# AetherMesh_Test_Fixture_LGA_V1_0.net
KiCad netlist of a schematic drawn in EAGLE
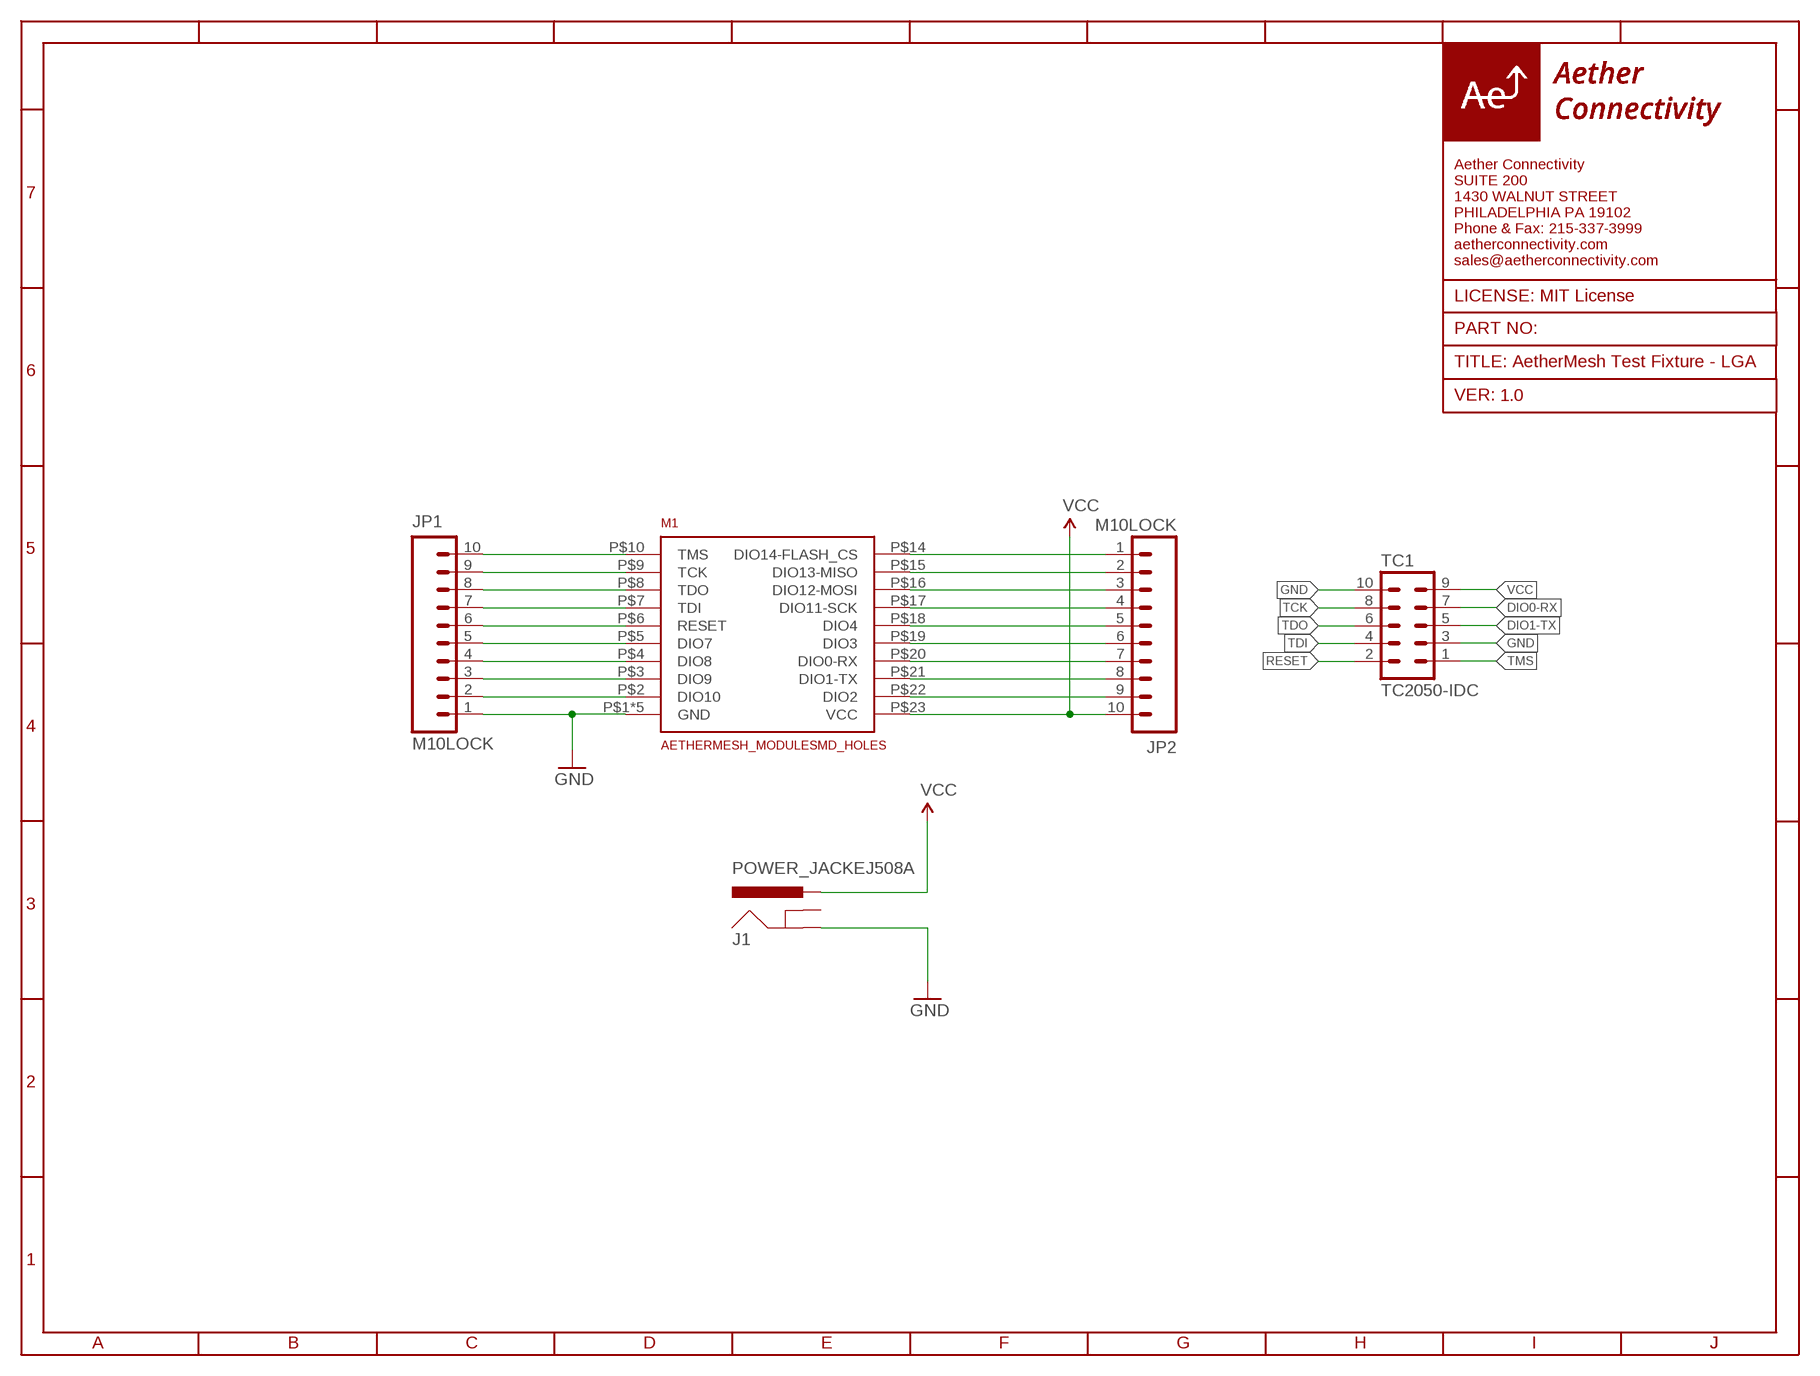
[diagram p0: schematic, sheet 1]

(export (version "E")
  (design (tool "Eeschema 10.0.6"))
  (components
    (comp (ref "J1")
      (value "POWER_JACKEJ508A")
      (footprint "eagle-import:DC_JACK_EJ508A")
      (libsource (lib "eagle-import") (part "POWER_JACKEJ508A"))
    )
    (comp (ref "JP1")
      (value "M10LOCK")
      (footprint "eagle-import:1X10_LOCK")
      (libsource (lib "eagle-import") (part "M10LOCK"))
    )
    (comp (ref "JP2")
      (value "M10LOCK")
      (footprint "eagle-import:1X10_LOCK")
      (libsource (lib "eagle-import") (part "M10LOCK"))
    )
    (comp (ref "M1")
      (value "AETHERMESH_MODULESMD_HOLES")
      (footprint "eagle-import:AETHERMESH_SMD_MOUNT_HOLES")
      (libsource (lib "eagle-import") (part "AETHERMESH_MODULESMD_HOLES"))
    )
    (comp (ref "TC1")
      (value "TC2050-IDC")
      (footprint "eagle-import:TC2050-IDC")
      (libsource (lib "eagle-import") (part "TC2050-IDC"))
    )
  )
  (nets
    (net (code "1") (name "DIO0-RX") (class "Default")
      (node (ref "JP2") (pin "7") (pinfunction "7_7") (pintype "passive"))
      (node (ref "M1") (pin "P$20") (pinfunction "DIO0-RX_P$20") (pintype "bidirectional"))
      (node (ref "TC1") (pin "7") (pinfunction "7_7") (pintype "passive"))
    )
    (net (code "2") (name "DIO1-TX") (class "Default")
      (node (ref "JP2") (pin "8") (pinfunction "8_8") (pintype "passive"))
      (node (ref "M1") (pin "P$21") (pinfunction "DIO1-TX_P$21") (pintype "bidirectional"))
      (node (ref "TC1") (pin "5") (pinfunction "5_5") (pintype "passive"))
    )
    (net (code "3") (name "GND") (class "Default")
      (node (ref "J1") (pin "1") (pinfunction "GND_1") (pintype "bidirectional"))
      (node (ref "JP1") (pin "1") (pinfunction "1_1") (pintype "passive"))
      (node (ref "M1") (pin "P$1") (pinfunction "GND_P$1") (pintype "bidirectional"))
      (node (ref "M1") (pin "P$11") (pinfunction "GND_P$11") (pintype "bidirectional"))
      (node (ref "M1") (pin "P$12") (pinfunction "GND_P$12") (pintype "bidirectional"))
      (node (ref "M1") (pin "P$13") (pinfunction "GND_P$13") (pintype "bidirectional"))
      (node (ref "M1") (pin "P$24") (pinfunction "GND_P$24") (pintype "bidirectional"))
      (node (ref "TC1") (pin "10") (pinfunction "10_10") (pintype "passive"))
      (node (ref "TC1") (pin "3") (pinfunction "3_3") (pintype "passive"))
    )
    (net (code "4") (name "Net-(M1-DIO2)") (class "Default")
      (node (ref "JP2") (pin "9") (pinfunction "9_9") (pintype "passive"))
      (node (ref "M1") (pin "P$22") (pinfunction "DIO2_P$22") (pintype "bidirectional"))
    )
    (net (code "5") (name "Net-(M1-DIO3)") (class "Default")
      (node (ref "JP2") (pin "6") (pinfunction "6_6") (pintype "passive"))
      (node (ref "M1") (pin "P$19") (pinfunction "DIO3_P$19") (pintype "bidirectional"))
    )
    (net (code "6") (name "Net-(M1-DIO4)") (class "Default")
      (node (ref "JP2") (pin "5") (pinfunction "5_5") (pintype "passive"))
      (node (ref "M1") (pin "P$18") (pinfunction "DIO4_P$18") (pintype "bidirectional"))
    )
    (net (code "7") (name "Net-(M1-DIO7)") (class "Default")
      (node (ref "JP1") (pin "5") (pinfunction "5_5") (pintype "passive"))
      (node (ref "M1") (pin "P$5") (pinfunction "DIO7_P$5") (pintype "bidirectional"))
    )
    (net (code "8") (name "Net-(M1-DIO8)") (class "Default")
      (node (ref "JP1") (pin "4") (pinfunction "4_4") (pintype "passive"))
      (node (ref "M1") (pin "P$4") (pinfunction "DIO8_P$4") (pintype "bidirectional"))
    )
    (net (code "9") (name "Net-(M1-DIO9)") (class "Default")
      (node (ref "JP1") (pin "3") (pinfunction "3_3") (pintype "passive"))
      (node (ref "M1") (pin "P$3") (pinfunction "DIO9_P$3") (pintype "bidirectional"))
    )
    (net (code "10") (name "Net-(M1-DIO10)") (class "Default")
      (node (ref "JP1") (pin "2") (pinfunction "2_2") (pintype "passive"))
      (node (ref "M1") (pin "P$2") (pinfunction "DIO10_P$2") (pintype "bidirectional"))
    )
    (net (code "11") (name "Net-(M1-DIO11-SCK)") (class "Default")
      (node (ref "JP2") (pin "4") (pinfunction "4_4") (pintype "passive"))
      (node (ref "M1") (pin "P$17") (pinfunction "DIO11-SCK_P$17") (pintype "bidirectional"))
    )
    (net (code "12") (name "Net-(M1-DIO12-MOSI)") (class "Default")
      (node (ref "JP2") (pin "3") (pinfunction "3_3") (pintype "passive"))
      (node (ref "M1") (pin "P$16") (pinfunction "DIO12-MOSI_P$16") (pintype "bidirectional"))
    )
    (net (code "13") (name "Net-(M1-DIO13-MISO)") (class "Default")
      (node (ref "JP2") (pin "2") (pinfunction "2_2") (pintype "passive"))
      (node (ref "M1") (pin "P$15") (pinfunction "DIO13-MISO_P$15") (pintype "bidirectional"))
    )
    (net (code "14") (name "Net-(M1-DIO14-FLASH_CS)") (class "Default")
      (node (ref "JP2") (pin "1") (pinfunction "1_1") (pintype "passive"))
      (node (ref "M1") (pin "P$14") (pinfunction "DIO14-FLASH_CS_P$14") (pintype "bidirectional"))
    )
    (net (code "15") (name "RESET") (class "Default")
      (node (ref "JP1") (pin "6") (pinfunction "6_6") (pintype "passive"))
      (node (ref "M1") (pin "P$6") (pinfunction "RESET_P$6") (pintype "bidirectional"))
      (node (ref "TC1") (pin "2") (pinfunction "2_2") (pintype "passive"))
    )
    (net (code "16") (name "TCK") (class "Default")
      (node (ref "JP1") (pin "9") (pinfunction "9_9") (pintype "passive"))
      (node (ref "M1") (pin "P$9") (pinfunction "TCK_P$9") (pintype "bidirectional"))
      (node (ref "TC1") (pin "8") (pinfunction "8_8") (pintype "passive"))
    )
    (net (code "17") (name "TDI") (class "Default")
      (node (ref "JP1") (pin "7") (pinfunction "7_7") (pintype "passive"))
      (node (ref "M1") (pin "P$7") (pinfunction "TDI_P$7") (pintype "bidirectional"))
      (node (ref "TC1") (pin "4") (pinfunction "4_4") (pintype "passive"))
    )
    (net (code "18") (name "TDO") (class "Default")
      (node (ref "JP1") (pin "8") (pinfunction "8_8") (pintype "passive"))
      (node (ref "M1") (pin "P$8") (pinfunction "TDO_P$8") (pintype "bidirectional"))
      (node (ref "TC1") (pin "6") (pinfunction "6_6") (pintype "passive"))
    )
    (net (code "19") (name "TMS") (class "Default")
      (node (ref "JP1") (pin "10") (pinfunction "10_10") (pintype "passive"))
      (node (ref "M1") (pin "P$10") (pinfunction "TMS_P$10") (pintype "bidirectional"))
      (node (ref "TC1") (pin "1") (pinfunction "1_1") (pintype "passive"))
    )
    (net (code "20") (name "VCC") (class "Default")
      (node (ref "J1") (pin "3") (pinfunction "PWR_3") (pintype "bidirectional"))
      (node (ref "JP2") (pin "10") (pinfunction "10_10") (pintype "passive"))
      (node (ref "M1") (pin "P$23") (pinfunction "VCC_P$23") (pintype "bidirectional"))
      (node (ref "TC1") (pin "9") (pinfunction "9_9") (pintype "passive"))
    )
    (net (code "21") (name "unconnected-(J1-GNDBREAK-Pad2)") (class "Default")
      (node (ref "J1") (pin "2") (pinfunction "GNDBREAK_2") (pintype "bidirectional"))
    )
  )
)
